# Analog_Filter.net
KiCad netlist of a schematic drawn in Altium Designer
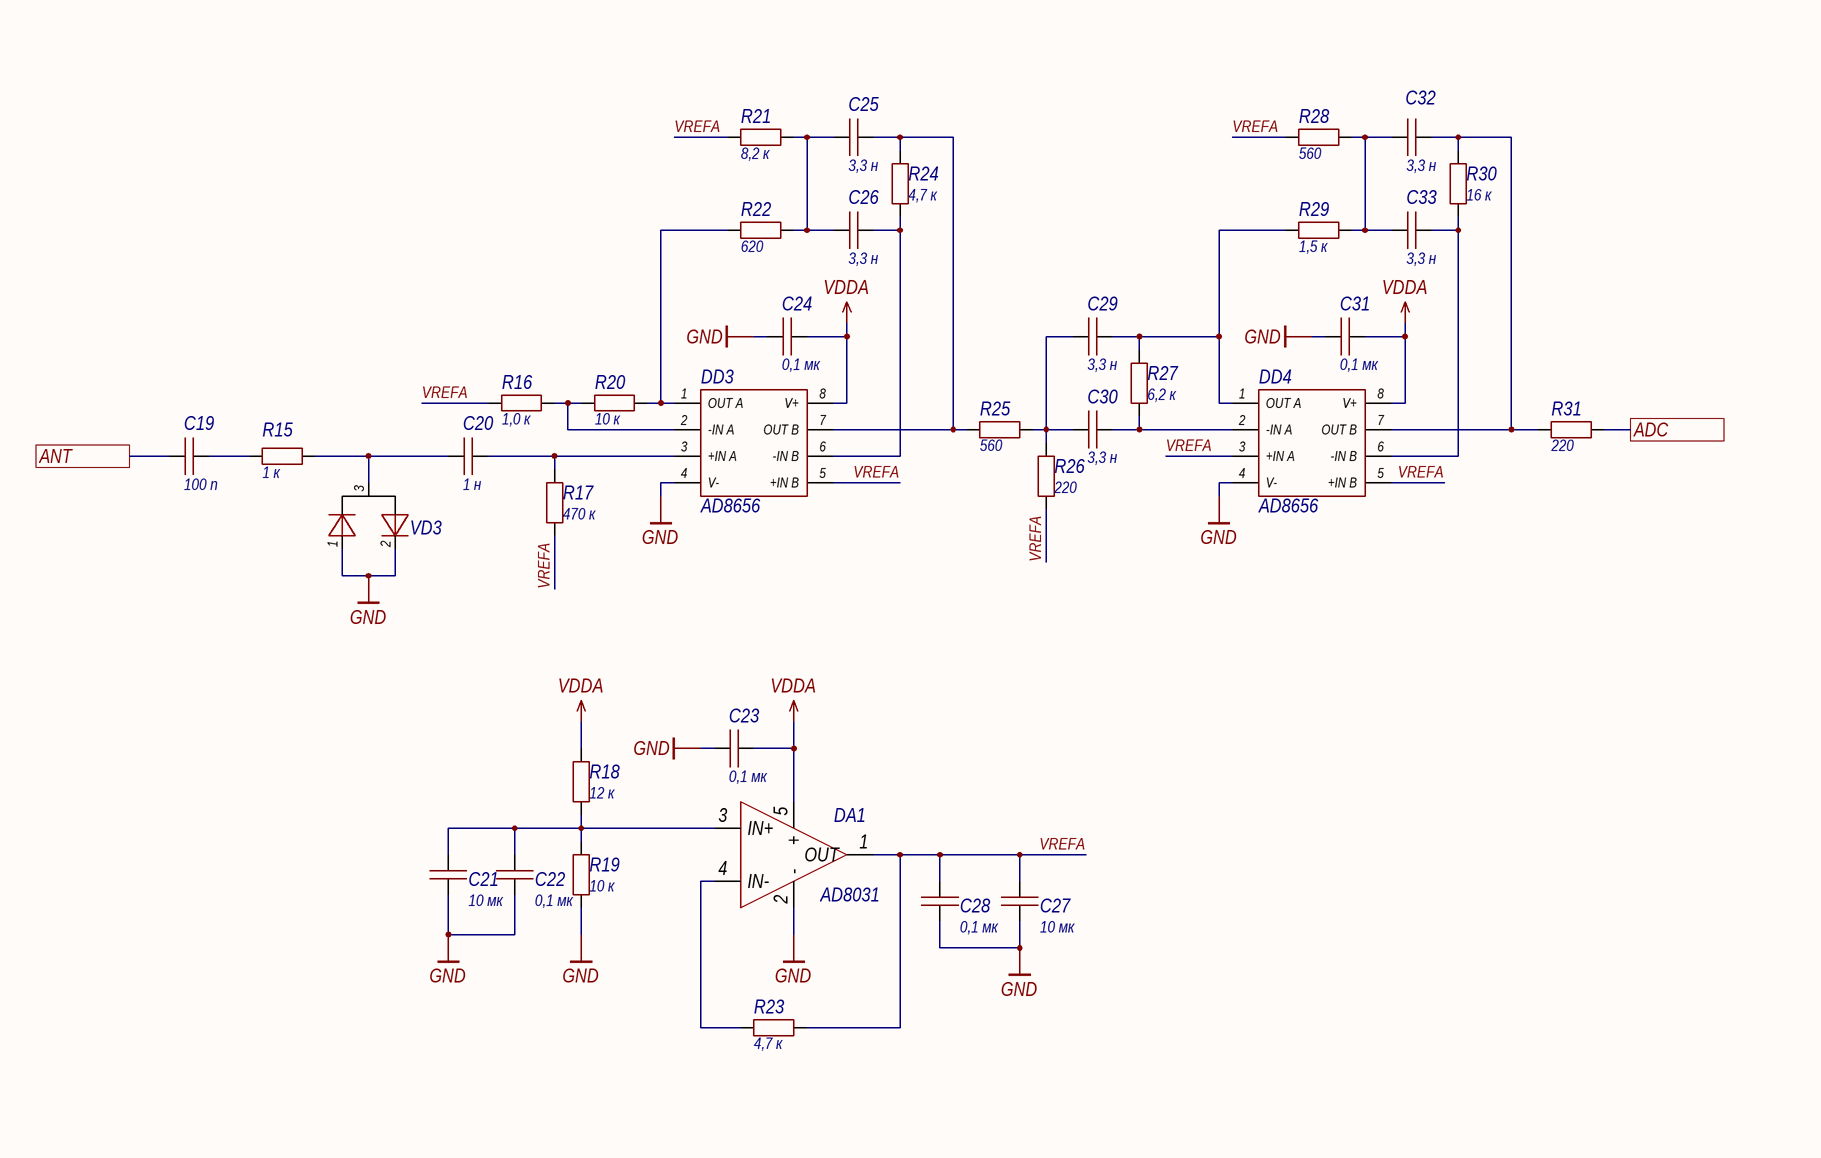
[diagram p0: Analog_Filter.SchDoc, left]
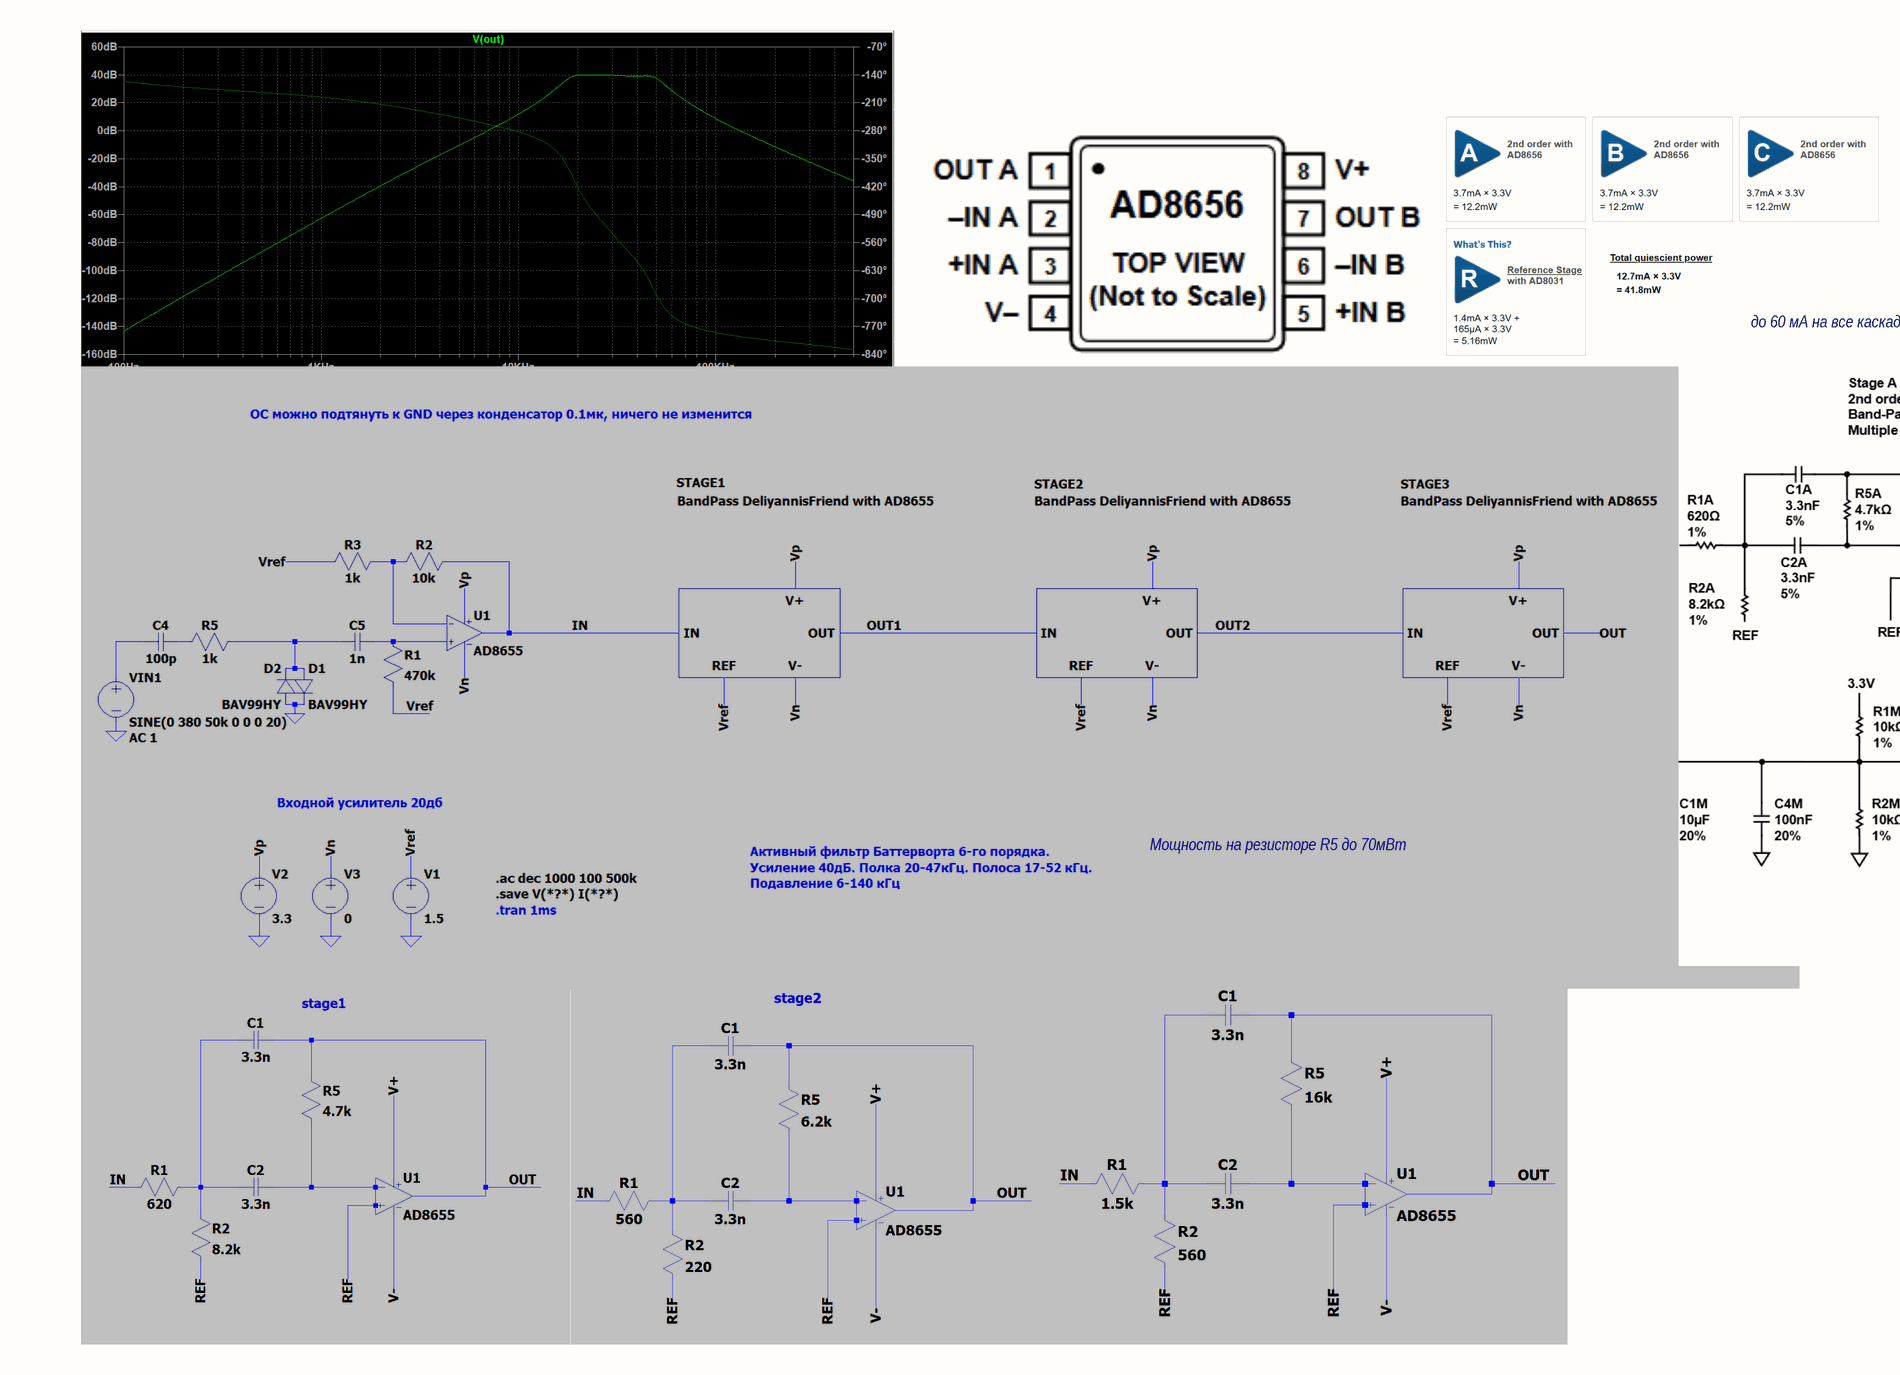
[diagram p1: Analog_Filter.SchDoc, middle]
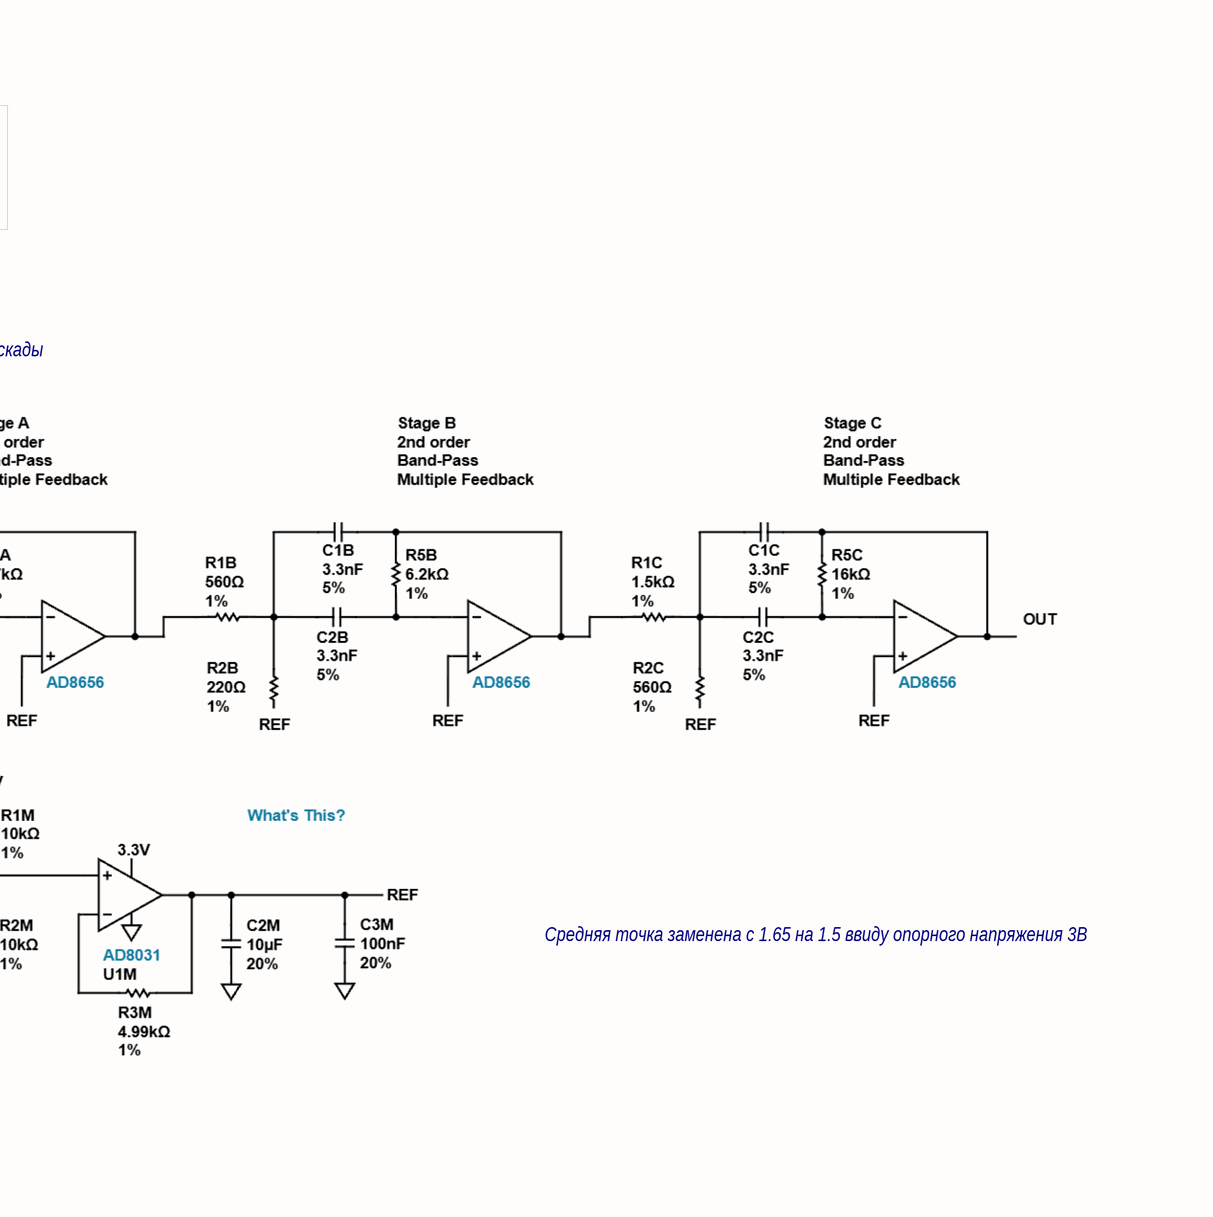
[diagram p2: Analog_Filter.SchDoc, right]

(export (version "E")
  (design (tool "Eeschema 10.0.6"))
  (components
    (comp (ref "C19")
      (value "100 п")
      (footprint "1206C")
      (description "Конденсатор 1206C ёмкостью 100 п 5%, 630 В, NP0")
      (fields
        (field (name "PART NUMBER") "Capacitor_100p_5_630V_NP0_1206C")
        (field (name "TOLERANCE") "5%")
        (field (name "АВТОР") "glebmih")
      )
      (libsource (lib "Hydrolib") (part "Capacitor"))
    )
    (comp (ref "C20")
      (value "1 н")
      (footprint "0603C")
      (description "Конденсатор 0603C ёмкостью 1 н 5%, 50 В, NP0")
      (fields
        (field (name "PART NUMBER") "Capacitor_1n_5_50V_NP0_0603C")
        (field (name "TOLERANCE") "5%")
        (field (name "АВТОР") "glebmih")
      )
      (libsource (lib "Hydrolib") (part "Capacitor"))
    )
    (comp (ref "C21")
      (value "10 мк")
      (footprint "0603C")
      (description "Конденсатор 0603C ёмкостью 10 мк 10%, 10 В, X7R")
      (fields
        (field (name "PART NUMBER") "Capacitor_10u_10_10V_X7R_0603C")
        (field (name "TOLERANCE") "10%")
        (field (name "АВТОР") "glebmih")
      )
      (libsource (lib "Hydrolib") (part "Capacitor"))
    )
    (comp (ref "C22")
      (value "0,1 мк")
      (footprint "0603C")
      (description "Конденсатор 0603C ёмкостью 0,1 мк 10%, 50 В, X7R")
      (fields (field (name "PART NUMBER") "Capacitor_0,1u_10_50V_X7R_0603C") (field (name "TOLERANCE") "10%"))
      (libsource (lib "Hydrolib") (part "Capacitor"))
    )
    (comp (ref "C23")
      (value "0,1 мк")
      (footprint "0603C")
      (description "Конденсатор 0603C ёмкостью 0,1 мк 10%, 50 В, X7R")
      (fields (field (name "PART NUMBER") "Capacitor_0,1u_10_50V_X7R_0603C") (field (name "TOLERANCE") "10%"))
      (libsource (lib "Hydrolib") (part "Capacitor"))
    )
    (comp (ref "C24")
      (value "0,1 мк")
      (footprint "0603C")
      (description "Конденсатор 0603C ёмкостью 0,1 мк 10%, 50 В, X7R")
      (fields (field (name "PART NUMBER") "Capacitor_0,1u_10_50V_X7R_0603C") (field (name "TOLERANCE") "10%"))
      (libsource (lib "Hydrolib") (part "Capacitor"))
    )
    (comp (ref "C25")
      (value "3,3 н")
      (footprint "0603C")
      (description "Конденсатор 0603C ёмкостью 3,3 н 5%, 50 В, NP0")
      (fields
        (field (name "PART NUMBER") "Capacitor_3.3n_5_50V_NP0_0603C")
        (field (name "TOLERANCE") "5%")
        (field (name "АВТОР") "glebmih")
      )
      (libsource (lib "Hydrolib") (part "Capacitor"))
    )
    (comp (ref "C26")
      (value "3,3 н")
      (footprint "0603C")
      (description "Конденсатор 0603C ёмкостью 3,3 н 5%, 50 В, NP0")
      (fields
        (field (name "PART NUMBER") "Capacitor_3.3n_5_50V_NP0_0603C")
        (field (name "TOLERANCE") "5%")
        (field (name "АВТОР") "glebmih")
      )
      (libsource (lib "Hydrolib") (part "Capacitor"))
    )
    (comp (ref "C27")
      (value "10 мк")
      (footprint "0603C")
      (description "Конденсатор 0603C ёмкостью 10 мк 10%, 10 В, X7R")
      (fields
        (field (name "PART NUMBER") "Capacitor_10u_10_10V_X7R_0603C")
        (field (name "TOLERANCE") "10%")
        (field (name "АВТОР") "glebmih")
      )
      (libsource (lib "Hydrolib") (part "Capacitor"))
    )
    (comp (ref "C28")
      (value "0,1 мк")
      (footprint "0603C")
      (description "Конденсатор 0603C ёмкостью 0,1 мк 10%, 50 В, X7R")
      (fields (field (name "PART NUMBER") "Capacitor_0,1u_10_50V_X7R_0603C") (field (name "TOLERANCE") "10%"))
      (libsource (lib "Hydrolib") (part "Capacitor"))
    )
    (comp (ref "C29")
      (value "3,3 н")
      (footprint "0603C")
      (description "Конденсатор 0603C ёмкостью 3,3 н 5%, 50 В, NP0")
      (fields
        (field (name "PART NUMBER") "Capacitor_3.3n_5_50V_NP0_0603C")
        (field (name "TOLERANCE") "5%")
        (field (name "АВТОР") "glebmih")
      )
      (libsource (lib "Hydrolib") (part "Capacitor"))
    )
    (comp (ref "C30")
      (value "3,3 н")
      (footprint "0603C")
      (description "Конденсатор 0603C ёмкостью 3,3 н 5%, 50 В, NP0")
      (fields
        (field (name "PART NUMBER") "Capacitor_3.3n_5_50V_NP0_0603C")
        (field (name "TOLERANCE") "5%")
        (field (name "АВТОР") "glebmih")
      )
      (libsource (lib "Hydrolib") (part "Capacitor"))
    )
    (comp (ref "C31")
      (value "0,1 мк")
      (footprint "0603C")
      (description "Конденсатор 0603C ёмкостью 0,1 мк 10%, 50 В, X7R")
      (fields (field (name "PART NUMBER") "Capacitor_0,1u_10_50V_X7R_0603C") (field (name "TOLERANCE") "10%"))
      (libsource (lib "Hydrolib") (part "Capacitor"))
    )
    (comp (ref "C32")
      (value "3,3 н")
      (footprint "0603C")
      (description "Конденсатор 0603C ёмкостью 3,3 н 5%, 50 В, NP0")
      (fields
        (field (name "PART NUMBER") "Capacitor_3.3n_5_50V_NP0_0603C")
        (field (name "TOLERANCE") "5%")
        (field (name "АВТОР") "glebmih")
      )
      (libsource (lib "Hydrolib") (part "Capacitor"))
    )
    (comp (ref "C33")
      (value "3,3 н")
      (footprint "0603C")
      (description "Конденсатор 0603C ёмкостью 3,3 н 5%, 50 В, NP0")
      (fields
        (field (name "PART NUMBER") "Capacitor_3.3n_5_50V_NP0_0603C")
        (field (name "TOLERANCE") "5%")
        (field (name "АВТОР") "glebmih")
      )
      (libsource (lib "Hydrolib") (part "Capacitor"))
    )
    (comp (ref "DA1")
      (value "AD8031")
      (footprint "SOT23-5")
      (description "Операционный усилитель, 80МГц, 1-канал, 35В/мкс, Voltage Feedback, Rail-to-Rail")
      (fields (field (name "АВТОР") "glebmih"))
      (libsource (lib "Hydrolib") (part "AD8031"))
    )
    (comp (ref "DD3")
      (value "AD8656")
      (footprint "SOIC-8")
      (description "Операционный усилитель 28МГц, CMOS, 2-канала, Rail-to-Rail")
      (fields (field (name "АВТОР") "glebmih"))
      (libsource (lib "Hydrolib") (part "AD8656"))
    )
    (comp (ref "DD4")
      (value "AD8656")
      (footprint "SOIC-8")
      (description "Операционный усилитель 28МГц, CMOS, 2-канала, Rail-to-Rail")
      (fields (field (name "АВТОР") "glebmih"))
      (libsource (lib "Hydrolib") (part "AD8656"))
    )
    (comp (ref "R15")
      (value "1 к")
      (footprint "0805R")
      (description "Резистор номиналом 1 кОм 1%")
      (fields
        (field (name "PART NUMBER") "Resistor_1k_0805")
        (field (name "TOLERANCE") "1%")
        (field (name "АВТОР") "glebmih")
      )
      (libsource (lib "") (part "Resistor_2"))
    )
    (comp (ref "R16")
      (value "1,0 к")
      (footprint "0603R")
      (description "Резистор номиналом 1,0 кОм 1%")
      (fields (field (name "PART NUMBER") "Resistor_1.0k_1_0603") (field (name "TOLERANCE") "1%"))
      (libsource (lib "") (part "Resistor_2"))
    )
    (comp (ref "R17")
      (value "470 к")
      (footprint "0603R")
      (description "Резистор номиналом 470 кОм 1%")
      (fields (field (name "PART NUMBER") "Resistor_470k_1_0603") (field (name "TOLERANCE") "1%"))
      (libsource (lib "Hydrolib") (part "Resistor"))
    )
    (comp (ref "R18")
      (value "12 к")
      (footprint "0603R")
      (description "Резистор номиналом 12 кОм 1%")
      (fields (field (name "PART NUMBER") "Resistor_12k_1_0603") (field (name "TOLERANCE") "1%"))
      (libsource (lib "Hydrolib") (part "Resistor"))
    )
    (comp (ref "R19")
      (value "10 к")
      (footprint "0603R")
      (description "Резистор номиналом 10 кОм 1%")
      (fields (field (name "PART NUMBER") "Resistor_10k_1_0603") (field (name "TOLERANCE") "1%"))
      (libsource (lib "Hydrolib") (part "Resistor"))
    )
    (comp (ref "R20")
      (value "10 к")
      (footprint "0603R")
      (description "Резистор номиналом 10 кОм 1%")
      (fields (field (name "PART NUMBER") "Resistor_10k_1_0603") (field (name "TOLERANCE") "1%"))
      (libsource (lib "") (part "Resistor_2"))
    )
    (comp (ref "R21")
      (value "8,2 к")
      (footprint "0603R")
      (description "Резистор номиналом 8,2 кОм 1%")
      (fields (field (name "PART NUMBER") "Resistor_8.2k_1_0603") (field (name "TOLERANCE") "1%"))
      (libsource (lib "") (part "Resistor_3"))
    )
    (comp (ref "R22")
      (value "620")
      (footprint "0603R")
      (description "Резистор номиналом 620 Ом 1%")
      (fields (field (name "PART NUMBER") "Resistor_620_1_0603") (field (name "TOLERANCE") "1%"))
      (libsource (lib "") (part "Resistor_2"))
    )
    (comp (ref "R23")
      (value "4,7 к")
      (footprint "0603R")
      (description "Резистор номиналом 4,7 кОм 1%")
      (fields (field (name "PART NUMBER") "Resistor_4.7k_1_0603") (field (name "TOLERANCE") "1%"))
      (libsource (lib "") (part "Resistor_2"))
    )
    (comp (ref "R24")
      (value "4,7 к")
      (footprint "0603R")
      (description "Резистор номиналом 4,7 кОм 1%")
      (fields (field (name "PART NUMBER") "Resistor_4.7k_1_0603") (field (name "TOLERANCE") "1%"))
      (libsource (lib "") (part "Resistor_1"))
    )
    (comp (ref "R25")
      (value "560")
      (footprint "0603R")
      (description "Резистор номиналом 560 Ом 1%")
      (fields (field (name "PART NUMBER") "Resistor_560_1_0603") (field (name "TOLERANCE") "1%"))
      (libsource (lib "") (part "Resistor_2"))
    )
    (comp (ref "R26")
      (value "220")
      (footprint "0603R")
      (description "Резистор номиналом 220 Ом 1%")
      (fields (field (name "PART NUMBER") "Resistor_220_1_0603") (field (name "TOLERANCE") "1%"))
      (libsource (lib "Hydrolib") (part "Resistor"))
    )
    (comp (ref "R27")
      (value "6,2 к")
      (footprint "0603R")
      (description "Резистор номиналом 6,2 кОм 1%")
      (fields (field (name "PART NUMBER") "Resistor_6.2k_1_0603") (field (name "TOLERANCE") "1%"))
      (libsource (lib "Hydrolib") (part "Resistor"))
    )
    (comp (ref "R28")
      (value "560")
      (footprint "0603R")
      (description "Резистор номиналом 560 Ом 1%")
      (fields (field (name "PART NUMBER") "Resistor_560_1_0603") (field (name "TOLERANCE") "1%"))
      (libsource (lib "") (part "Resistor_2"))
    )
    (comp (ref "R29")
      (value "1,5 к")
      (footprint "0603R")
      (description "Резистор номиналом 1,5 кОм 1%")
      (fields (field (name "PART NUMBER") "Resistor_1.5k_1_0603") (field (name "TOLERANCE") "1%"))
      (libsource (lib "") (part "Resistor_2"))
    )
    (comp (ref "R30")
      (value "16 к")
      (footprint "0603R")
      (description "Резистор номиналом 16 кОм 1%")
      (fields (field (name "PART NUMBER") "Resistor_16k_1_0603") (field (name "TOLERANCE") "1%"))
      (libsource (lib "Hydrolib") (part "Resistor"))
    )
    (comp (ref "R31")
      (value "220")
      (footprint "0603R")
      (description "Резистор номиналом 220 Ом 1%")
      (fields (field (name "PART NUMBER") "Resistor_220_1_0603") (field (name "TOLERANCE") "1%"))
      (libsource (lib "") (part "Resistor_2"))
    )
    (comp (ref "VD3")
      (value "BAV99")
      (footprint "SOT23-3")
      (description "Диод импульсный, 2 х 0.2А, 70В, последовательное включение")
      (fields (field (name "АВТОР") "glebmih"))
      (libsource (lib "Hydrolib") (part "Rectifier_diode_2"))
    )
  )
  (nets
    (net (code "1") (name "/ADC") (class "Default")
      (node (ref "R31") (pin "2") (pinfunction "2_2") (pintype "passive"))
    )
    (net (code "2") (name "/ANT") (class "Default")
      (node (ref "C19") (pin "1") (pinfunction "1_1") (pintype "passive"))
    )
    (net (code "3") (name "/VREFA") (class "Default")
      (node (ref "C27") (pin "2") (pinfunction "2_2") (pintype "passive"))
      (node (ref "C28") (pin "2") (pinfunction "2_2") (pintype "passive"))
      (node (ref "DA1") (pin "1") (pinfunction "OUT_1") (pintype "passive"))
      (node (ref "DD3") (pin "5") (pinfunction "+IN_B_5") (pintype "passive"))
      (node (ref "DD4") (pin "3") (pinfunction "+IN_A_3") (pintype "passive"))
      (node (ref "DD4") (pin "5") (pinfunction "+IN_B_5") (pintype "passive"))
      (node (ref "R16") (pin "1") (pinfunction "1_1") (pintype "passive"))
      (node (ref "R17") (pin "1") (pinfunction "1_1") (pintype "passive"))
      (node (ref "R21") (pin "2") (pinfunction "2_2") (pintype "passive"))
      (node (ref "R23") (pin "2") (pinfunction "2_2") (pintype "passive"))
      (node (ref "R26") (pin "1") (pinfunction "1_1") (pintype "passive"))
      (node (ref "R28") (pin "1") (pinfunction "1_1") (pintype "passive"))
    )
    (net (code "4") (name "GND") (class "Default")
      (node (ref "C21") (pin "1") (pinfunction "1_1") (pintype "passive"))
      (node (ref "C22") (pin "1") (pinfunction "1_1") (pintype "passive"))
      (node (ref "C23") (pin "1") (pinfunction "1_1") (pintype "passive"))
      (node (ref "C24") (pin "1") (pinfunction "1_1") (pintype "passive"))
      (node (ref "C27") (pin "1") (pinfunction "1_1") (pintype "passive"))
      (node (ref "C28") (pin "1") (pinfunction "1_1") (pintype "passive"))
      (node (ref "C31") (pin "1") (pinfunction "1_1") (pintype "passive"))
      (node (ref "DA1") (pin "2") (pinfunction "-_2") (pintype "passive"))
      (node (ref "DD3") (pin "4") (pinfunction "V-_4") (pintype "passive"))
      (node (ref "DD4") (pin "4") (pinfunction "V-_4") (pintype "passive"))
      (node (ref "R19") (pin "1") (pinfunction "1_1") (pintype "passive"))
      (node (ref "VD3") (pin "1") (pinfunction "1_1") (pintype "passive"))
      (node (ref "VD3") (pin "2") (pinfunction "2_2") (pintype "passive"))
    )
    (net (code "5") (name "Net-(C19-Pad2)") (class "Default")
      (node (ref "C19") (pin "2") (pinfunction "2_2") (pintype "passive"))
      (node (ref "R15") (pin "1") (pinfunction "1_1") (pintype "passive"))
    )
    (net (code "6") (name "Net-(C20-Pad1)") (class "Default")
      (node (ref "C20") (pin "1") (pinfunction "1_1") (pintype "passive"))
      (node (ref "R15") (pin "2") (pinfunction "2_2") (pintype "passive"))
      (node (ref "VD3") (pin "3") (pinfunction "3_3") (pintype "passive"))
    )
    (net (code "7") (name "Net-(C25-Pad1)") (class "Default")
      (node (ref "C25") (pin "1") (pinfunction "1_1") (pintype "passive"))
      (node (ref "C26") (pin "1") (pinfunction "1_1") (pintype "passive"))
      (node (ref "R21") (pin "1") (pinfunction "1_1") (pintype "passive"))
      (node (ref "R22") (pin "2") (pinfunction "2_2") (pintype "passive"))
    )
    (net (code "8") (name "Net-(C29-Pad1)") (class "Default")
      (node (ref "C29") (pin "1") (pinfunction "1_1") (pintype "passive"))
      (node (ref "C30") (pin "1") (pinfunction "1_1") (pintype "passive"))
      (node (ref "R25") (pin "2") (pinfunction "2_2") (pintype "passive"))
      (node (ref "R26") (pin "2") (pinfunction "2_2") (pintype "passive"))
    )
    (net (code "9") (name "Net-(C32-Pad1)") (class "Default")
      (node (ref "C32") (pin "1") (pinfunction "1_1") (pintype "passive"))
      (node (ref "C33") (pin "1") (pinfunction "1_1") (pintype "passive"))
      (node (ref "R28") (pin "2") (pinfunction "2_2") (pintype "passive"))
      (node (ref "R29") (pin "2") (pinfunction "2_2") (pintype "passive"))
    )
    (net (code "10") (name "Net-(DA1-IN+)") (class "Default")
      (node (ref "C21") (pin "2") (pinfunction "2_2") (pintype "passive"))
      (node (ref "C22") (pin "2") (pinfunction "2_2") (pintype "passive"))
      (node (ref "DA1") (pin "3") (pinfunction "IN+_3") (pintype "passive"))
      (node (ref "R18") (pin "1") (pinfunction "1_1") (pintype "passive"))
      (node (ref "R19") (pin "2") (pinfunction "2_2") (pintype "passive"))
    )
    (net (code "11") (name "Net-(DA1-IN-)") (class "Default")
      (node (ref "DA1") (pin "4") (pinfunction "IN-_4") (pintype "passive"))
      (node (ref "R23") (pin "1") (pinfunction "1_1") (pintype "passive"))
    )
    (net (code "12") (name "Net-(DD3-+IN_A)") (class "Default")
      (node (ref "C20") (pin "2") (pinfunction "2_2") (pintype "passive"))
      (node (ref "DD3") (pin "3") (pinfunction "+IN_A_3") (pintype "passive"))
      (node (ref "R17") (pin "2") (pinfunction "2_2") (pintype "passive"))
    )
    (net (code "13") (name "Net-(DD3--IN_A)") (class "Default")
      (node (ref "DD3") (pin "2") (pinfunction "-IN_A_2") (pintype "passive"))
      (node (ref "R16") (pin "2") (pinfunction "2_2") (pintype "passive"))
      (node (ref "R20") (pin "1") (pinfunction "1_1") (pintype "passive"))
    )
    (net (code "14") (name "Net-(DD3--IN_B)") (class "Default")
      (node (ref "C26") (pin "2") (pinfunction "2_2") (pintype "passive"))
      (node (ref "DD3") (pin "6") (pinfunction "-IN_B_6") (pintype "passive"))
      (node (ref "R24") (pin "2") (pinfunction "2_2") (pintype "passive"))
    )
    (net (code "15") (name "Net-(DD3-OUT_A)") (class "Default")
      (node (ref "DD3") (pin "1") (pinfunction "OUT_A_1") (pintype "passive"))
      (node (ref "R20") (pin "2") (pinfunction "2_2") (pintype "passive"))
      (node (ref "R22") (pin "1") (pinfunction "1_1") (pintype "passive"))
    )
    (net (code "16") (name "Net-(DD3-OUT_B)") (class "Default")
      (node (ref "C25") (pin "2") (pinfunction "2_2") (pintype "passive"))
      (node (ref "DD3") (pin "7") (pinfunction "OUT_B_7") (pintype "passive"))
      (node (ref "R24") (pin "1") (pinfunction "1_1") (pintype "passive"))
      (node (ref "R25") (pin "1") (pinfunction "1_1") (pintype "passive"))
    )
    (net (code "17") (name "Net-(DD4--IN_A)") (class "Default")
      (node (ref "C30") (pin "2") (pinfunction "2_2") (pintype "passive"))
      (node (ref "DD4") (pin "2") (pinfunction "-IN_A_2") (pintype "passive"))
      (node (ref "R27") (pin "1") (pinfunction "1_1") (pintype "passive"))
    )
    (net (code "18") (name "Net-(DD4--IN_B)") (class "Default")
      (node (ref "C33") (pin "2") (pinfunction "2_2") (pintype "passive"))
      (node (ref "DD4") (pin "6") (pinfunction "-IN_B_6") (pintype "passive"))
      (node (ref "R30") (pin "1") (pinfunction "1_1") (pintype "passive"))
    )
    (net (code "19") (name "Net-(DD4-OUT_A)") (class "Default")
      (node (ref "C29") (pin "2") (pinfunction "2_2") (pintype "passive"))
      (node (ref "DD4") (pin "1") (pinfunction "OUT_A_1") (pintype "passive"))
      (node (ref "R27") (pin "2") (pinfunction "2_2") (pintype "passive"))
      (node (ref "R29") (pin "1") (pinfunction "1_1") (pintype "passive"))
    )
    (net (code "20") (name "Net-(DD4-OUT_B)") (class "Default")
      (node (ref "C32") (pin "2") (pinfunction "2_2") (pintype "passive"))
      (node (ref "DD4") (pin "7") (pinfunction "OUT_B_7") (pintype "passive"))
      (node (ref "R30") (pin "2") (pinfunction "2_2") (pintype "passive"))
      (node (ref "R31") (pin "1") (pinfunction "1_1") (pintype "passive"))
    )
    (net (code "21") (name "VDDA") (class "Default")
      (node (ref "C23") (pin "2") (pinfunction "2_2") (pintype "passive"))
      (node (ref "C24") (pin "2") (pinfunction "2_2") (pintype "passive"))
      (node (ref "C31") (pin "2") (pinfunction "2_2") (pintype "passive"))
      (node (ref "DA1") (pin "5") (pinfunction "+_5") (pintype "passive"))
      (node (ref "DD3") (pin "8") (pinfunction "V+_8") (pintype "passive"))
      (node (ref "DD4") (pin "8") (pinfunction "V+_8") (pintype "passive"))
      (node (ref "R18") (pin "2") (pinfunction "2_2") (pintype "passive"))
    )
  )
)
